# 505153_2_1.net
KiCad netlist of a schematic drawn in Altium Designer
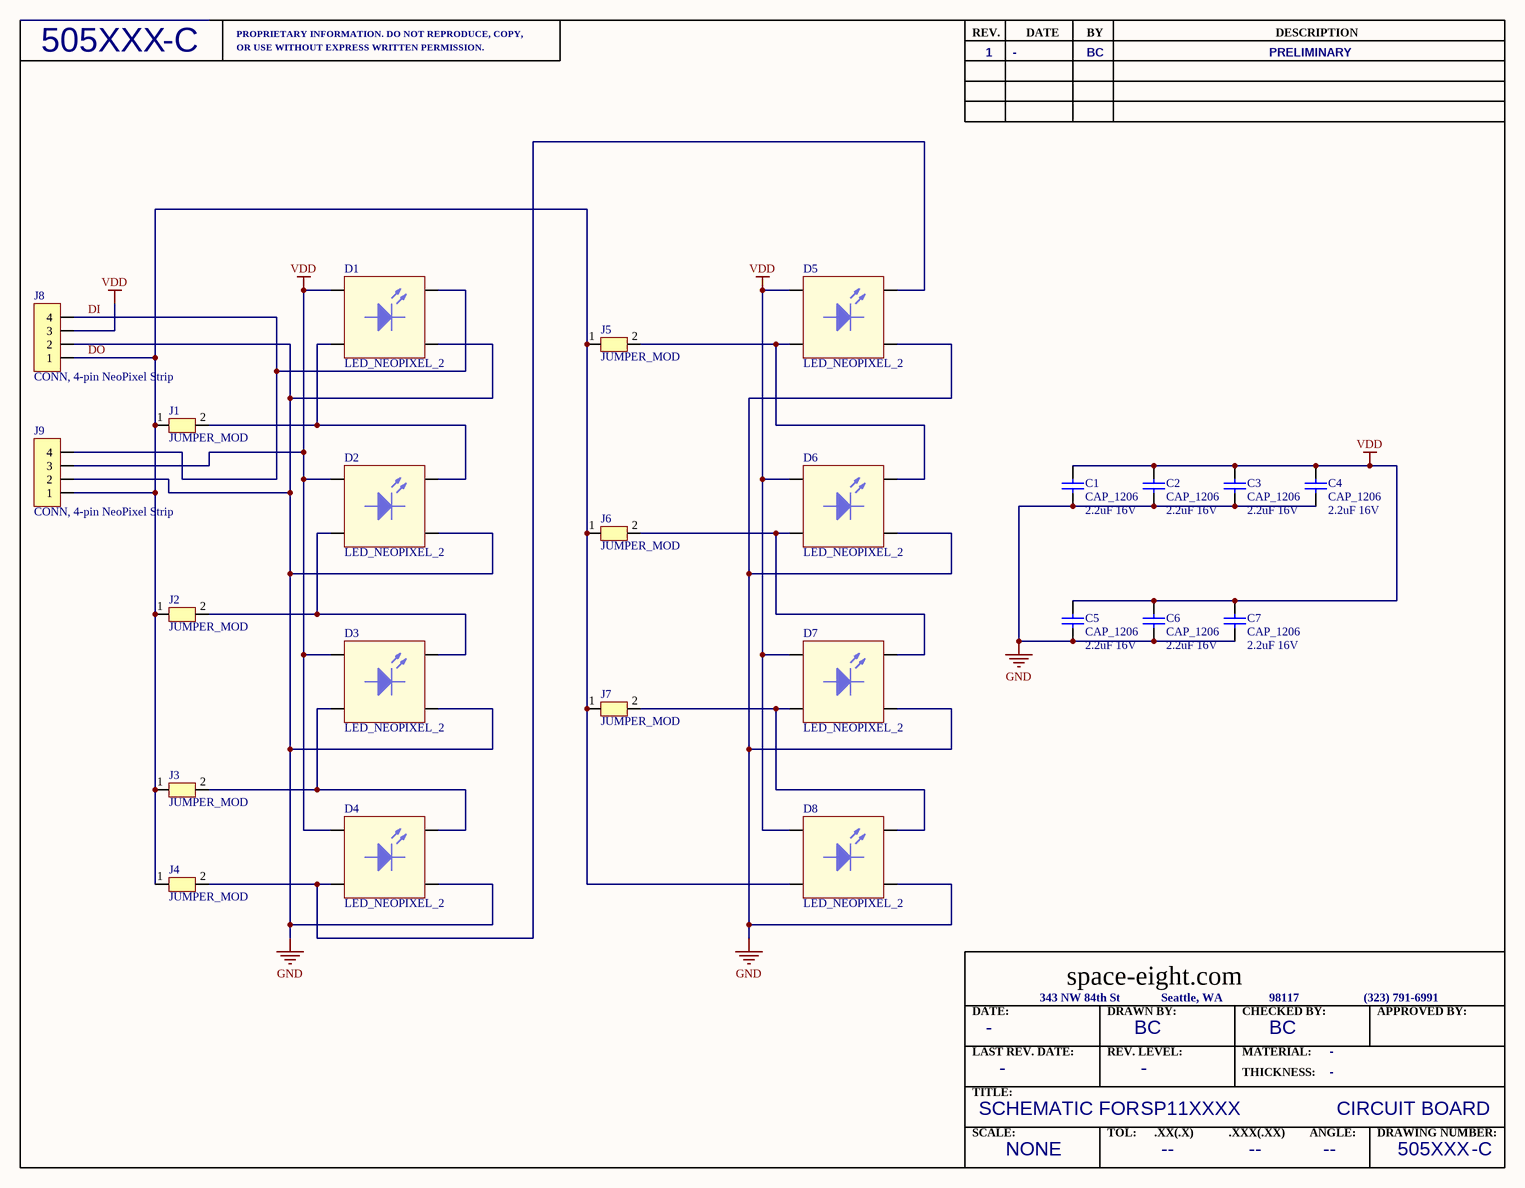
[diagram p0: 505153_2_1.SchDoc]

(export (version "E")
  (design (tool "Eeschema 10.0.6"))
  (components
    (comp (ref "C1")
      (value "CAP_1206")
      (footprint "SMT_1206_MOD")
      (description "CAP")
      (fields
        (field (name "MANUFACTURER") "Generic Components")
        (field (name "ALTIUM_VALUE") "2.2uF 16V")
        (field (name "PUBLISHER") "Altium Limited")
      )
      (libsource (lib "Custom_Lib_2") (part "CAP_1206"))
    )
    (comp (ref "C2")
      (value "CAP_1206")
      (footprint "SMT_1206_MOD")
      (description "CAP")
      (fields
        (field (name "MANUFACTURER") "Generic Components")
        (field (name "ALTIUM_VALUE") "2.2uF 16V")
        (field (name "PUBLISHER") "Altium Limited")
      )
      (libsource (lib "Custom_Lib_2") (part "CAP_1206"))
    )
    (comp (ref "C3")
      (value "CAP_1206")
      (footprint "SMT_1206_MOD")
      (description "CAP")
      (fields
        (field (name "MANUFACTURER") "Generic Components")
        (field (name "ALTIUM_VALUE") "2.2uF 16V")
        (field (name "PUBLISHER") "Altium Limited")
      )
      (libsource (lib "Custom_Lib_2") (part "CAP_1206"))
    )
    (comp (ref "C4")
      (value "CAP_1206")
      (footprint "SMT_1206_MOD")
      (description "CAP")
      (fields
        (field (name "MANUFACTURER") "Generic Components")
        (field (name "ALTIUM_VALUE") "2.2uF 16V")
        (field (name "PUBLISHER") "Altium Limited")
      )
      (libsource (lib "Custom_Lib_2") (part "CAP_1206"))
    )
    (comp (ref "C5")
      (value "CAP_1206")
      (footprint "SMT_1206_MOD")
      (description "CAP")
      (fields
        (field (name "MANUFACTURER") "Generic Components")
        (field (name "ALTIUM_VALUE") "2.2uF 16V")
        (field (name "PUBLISHER") "Altium Limited")
      )
      (libsource (lib "Custom_Lib_2") (part "CAP_1206"))
    )
    (comp (ref "C6")
      (value "CAP_1206")
      (footprint "SMT_1206_MOD")
      (description "CAP")
      (fields
        (field (name "MANUFACTURER") "Generic Components")
        (field (name "ALTIUM_VALUE") "2.2uF 16V")
        (field (name "PUBLISHER") "Altium Limited")
      )
      (libsource (lib "Custom_Lib_2") (part "CAP_1206"))
    )
    (comp (ref "C7")
      (value "CAP_1206")
      (footprint "SMT_1206_MOD")
      (description "CAP")
      (fields
        (field (name "MANUFACTURER") "Generic Components")
        (field (name "ALTIUM_VALUE") "2.2uF 16V")
        (field (name "PUBLISHER") "Altium Limited")
      )
      (libsource (lib "Custom_Lib_2") (part "CAP_1206"))
    )
    (comp (ref "D1")
      (value "LED_NEOPIXEL_2")
      (footprint "NEOPIXEL_2")
      (description "RGB NEOPIXEL")
      (fields (field (name "MANUFACTURER") "Generic Components") (field (name "PUBLISHER") "Altium Limited"))
      (libsource (lib "Custom_Lib_2") (part "LED_NEOPIXEL_2"))
    )
    (comp (ref "D2")
      (value "LED_NEOPIXEL_2")
      (footprint "NEOPIXEL_2")
      (description "RGB NEOPIXEL")
      (fields (field (name "MANUFACTURER") "Generic Components") (field (name "PUBLISHER") "Altium Limited"))
      (libsource (lib "Custom_Lib_2") (part "LED_NEOPIXEL_2"))
    )
    (comp (ref "D3")
      (value "LED_NEOPIXEL_2")
      (footprint "NEOPIXEL_2")
      (description "RGB NEOPIXEL")
      (fields (field (name "MANUFACTURER") "Generic Components") (field (name "PUBLISHER") "Altium Limited"))
      (libsource (lib "Custom_Lib_2") (part "LED_NEOPIXEL_2"))
    )
    (comp (ref "D4")
      (value "LED_NEOPIXEL_2")
      (footprint "NEOPIXEL_2")
      (description "RGB NEOPIXEL")
      (fields (field (name "MANUFACTURER") "Generic Components") (field (name "PUBLISHER") "Altium Limited"))
      (libsource (lib "Custom_Lib_2") (part "LED_NEOPIXEL_2"))
    )
    (comp (ref "D5")
      (value "LED_NEOPIXEL_2")
      (footprint "NEOPIXEL_2")
      (description "RGB NEOPIXEL")
      (fields (field (name "MANUFACTURER") "Generic Components") (field (name "PUBLISHER") "Altium Limited"))
      (libsource (lib "Custom_Lib_2") (part "LED_NEOPIXEL_2"))
    )
    (comp (ref "D6")
      (value "LED_NEOPIXEL_2")
      (footprint "NEOPIXEL_2")
      (description "RGB NEOPIXEL")
      (fields (field (name "MANUFACTURER") "Generic Components") (field (name "PUBLISHER") "Altium Limited"))
      (libsource (lib "Custom_Lib_2") (part "LED_NEOPIXEL_2"))
    )
    (comp (ref "D7")
      (value "LED_NEOPIXEL_2")
      (footprint "NEOPIXEL_2")
      (description "RGB NEOPIXEL")
      (fields (field (name "MANUFACTURER") "Generic Components") (field (name "PUBLISHER") "Altium Limited"))
      (libsource (lib "Custom_Lib_2") (part "LED_NEOPIXEL_2"))
    )
    (comp (ref "D8")
      (value "LED_NEOPIXEL_2")
      (footprint "NEOPIXEL_2")
      (description "RGB NEOPIXEL")
      (fields (field (name "MANUFACTURER") "Generic Components") (field (name "PUBLISHER") "Altium Limited"))
      (libsource (lib "Custom_Lib_2") (part "LED_NEOPIXEL_2"))
    )
    (comp (ref "J1")
      (value "JUMPER_MOD")
      (footprint "JUMPER_SMT")
      (libsource (lib "Custom_Lib_2") (part "JUMPER_MOD"))
    )
    (comp (ref "J2")
      (value "JUMPER_MOD")
      (footprint "JUMPER_SMT")
      (libsource (lib "Custom_Lib_2") (part "JUMPER_MOD"))
    )
    (comp (ref "J3")
      (value "JUMPER_MOD")
      (footprint "JUMPER_SMT")
      (libsource (lib "Custom_Lib_2") (part "JUMPER_MOD"))
    )
    (comp (ref "J4")
      (value "JUMPER_MOD")
      (footprint "JUMPER_SMT")
      (libsource (lib "Custom_Lib_2") (part "JUMPER_MOD"))
    )
    (comp (ref "J5")
      (value "JUMPER_MOD")
      (footprint "JUMPER_SMT")
      (libsource (lib "Custom_Lib_2") (part "JUMPER_MOD"))
    )
    (comp (ref "J6")
      (value "JUMPER_MOD")
      (footprint "JUMPER_SMT")
      (libsource (lib "Custom_Lib_2") (part "JUMPER_MOD"))
    )
    (comp (ref "J7")
      (value "JUMPER_MOD")
      (footprint "JUMPER_SMT")
      (libsource (lib "Custom_Lib_2") (part "JUMPER_MOD"))
    )
    (comp (ref "J8")
      (value "CONN, 4-pin NeoPixel Strip")
      (footprint "CONN_NEOPIXEL_1")
      (description "Conn Neopixel Strip")
      (fields (field (name "PUBLISHER") "Altium Limited"))
      (libsource (lib "Custom_Lib_2") (part "CONN, 4-pin NeoPixel Strip"))
    )
    (comp (ref "J9")
      (value "CONN, 4-pin NeoPixel Strip")
      (footprint "CONN_NEOPIXEL_1")
      (description "Conn Neopixel Strip")
      (fields (field (name "PUBLISHER") "Altium Limited"))
      (libsource (lib "Custom_Lib_2") (part "CONN, 4-pin NeoPixel Strip"))
    )
  )
  (nets
    (net (code "1") (name "/DI") (class "Default")
      (node (ref "D1") (pin "2") (pinfunction "DI_2") (pintype "passive"))
      (node (ref "J8") (pin "4") (pinfunction "4_4") (pintype "passive"))
      (node (ref "J9") (pin "4") (pinfunction "4_4") (pintype "passive"))
    )
    (net (code "2") (name "/DO") (class "Default")
      (node (ref "D8") (pin "4") (pinfunction "DO_4") (pintype "passive"))
      (node (ref "J1") (pin "1") (pinfunction "I/_1") (pintype "passive"))
      (node (ref "J2") (pin "1") (pinfunction "I/_1") (pintype "passive"))
      (node (ref "J3") (pin "1") (pinfunction "I/_1") (pintype "passive"))
      (node (ref "J4") (pin "1") (pinfunction "I/_1") (pintype "passive"))
      (node (ref "J5") (pin "1") (pinfunction "I/_1") (pintype "passive"))
      (node (ref "J6") (pin "1") (pinfunction "I/_1") (pintype "passive"))
      (node (ref "J7") (pin "1") (pinfunction "I/_1") (pintype "passive"))
      (node (ref "J8") (pin "1") (pinfunction "1_1") (pintype "passive"))
      (node (ref "J9") (pin "1") (pinfunction "1_1") (pintype "passive"))
    )
    (net (code "3") (name "GND") (class "Default")
      (node (ref "C1") (pin "1") (pinfunction "1_1") (pintype "passive"))
      (node (ref "C2") (pin "1") (pinfunction "1_1") (pintype "passive"))
      (node (ref "C3") (pin "1") (pinfunction "1_1") (pintype "passive"))
      (node (ref "C4") (pin "1") (pinfunction "1_1") (pintype "passive"))
      (node (ref "C5") (pin "1") (pinfunction "1_1") (pintype "passive"))
      (node (ref "C6") (pin "1") (pinfunction "1_1") (pintype "passive"))
      (node (ref "C7") (pin "1") (pinfunction "1_1") (pintype "passive"))
      (node (ref "D1") (pin "1") (pinfunction "GND_1") (pintype "passive"))
      (node (ref "D2") (pin "1") (pinfunction "GND_1") (pintype "passive"))
      (node (ref "D3") (pin "1") (pinfunction "GND_1") (pintype "passive"))
      (node (ref "D4") (pin "1") (pinfunction "GND_1") (pintype "passive"))
      (node (ref "D5") (pin "1") (pinfunction "GND_1") (pintype "passive"))
      (node (ref "D6") (pin "1") (pinfunction "GND_1") (pintype "passive"))
      (node (ref "D7") (pin "1") (pinfunction "GND_1") (pintype "passive"))
      (node (ref "D8") (pin "1") (pinfunction "GND_1") (pintype "passive"))
      (node (ref "J8") (pin "2") (pinfunction "2_2") (pintype "passive"))
      (node (ref "J9") (pin "2") (pinfunction "2_2") (pintype "passive"))
    )
    (net (code "4") (name "Net-(D1-DO)") (class "Default")
      (node (ref "D1") (pin "4") (pinfunction "DO_4") (pintype "passive"))
      (node (ref "D2") (pin "2") (pinfunction "DI_2") (pintype "passive"))
      (node (ref "J1") (pin "2") (pinfunction "O_2") (pintype "passive"))
    )
    (net (code "5") (name "Net-(D2-DO)") (class "Default")
      (node (ref "D2") (pin "4") (pinfunction "DO_4") (pintype "passive"))
      (node (ref "D3") (pin "2") (pinfunction "DI_2") (pintype "passive"))
      (node (ref "J2") (pin "2") (pinfunction "O_2") (pintype "passive"))
    )
    (net (code "6") (name "Net-(D3-DO)") (class "Default")
      (node (ref "D3") (pin "4") (pinfunction "DO_4") (pintype "passive"))
      (node (ref "D4") (pin "2") (pinfunction "DI_2") (pintype "passive"))
      (node (ref "J3") (pin "2") (pinfunction "O_2") (pintype "passive"))
    )
    (net (code "7") (name "Net-(D4-DO)") (class "Default")
      (node (ref "D4") (pin "4") (pinfunction "DO_4") (pintype "passive"))
      (node (ref "D5") (pin "2") (pinfunction "DI_2") (pintype "passive"))
      (node (ref "J4") (pin "2") (pinfunction "O_2") (pintype "passive"))
    )
    (net (code "8") (name "Net-(D5-DO)") (class "Default")
      (node (ref "D5") (pin "4") (pinfunction "DO_4") (pintype "passive"))
      (node (ref "D6") (pin "2") (pinfunction "DI_2") (pintype "passive"))
      (node (ref "J5") (pin "2") (pinfunction "O_2") (pintype "passive"))
    )
    (net (code "9") (name "Net-(D6-DO)") (class "Default")
      (node (ref "D6") (pin "4") (pinfunction "DO_4") (pintype "passive"))
      (node (ref "D7") (pin "2") (pinfunction "DI_2") (pintype "passive"))
      (node (ref "J6") (pin "2") (pinfunction "O_2") (pintype "passive"))
    )
    (net (code "10") (name "Net-(D7-DO)") (class "Default")
      (node (ref "D7") (pin "4") (pinfunction "DO_4") (pintype "passive"))
      (node (ref "D8") (pin "2") (pinfunction "DI_2") (pintype "passive"))
      (node (ref "J7") (pin "2") (pinfunction "O_2") (pintype "passive"))
    )
    (net (code "11") (name "VDD") (class "Default")
      (node (ref "C1") (pin "2") (pinfunction "2_2") (pintype "passive"))
      (node (ref "C2") (pin "2") (pinfunction "2_2") (pintype "passive"))
      (node (ref "C3") (pin "2") (pinfunction "2_2") (pintype "passive"))
      (node (ref "C4") (pin "2") (pinfunction "2_2") (pintype "passive"))
      (node (ref "C5") (pin "2") (pinfunction "2_2") (pintype "passive"))
      (node (ref "C6") (pin "2") (pinfunction "2_2") (pintype "passive"))
      (node (ref "C7") (pin "2") (pinfunction "2_2") (pintype "passive"))
      (node (ref "D1") (pin "3") (pinfunction "VDD_3") (pintype "passive"))
      (node (ref "D2") (pin "3") (pinfunction "VDD_3") (pintype "passive"))
      (node (ref "D3") (pin "3") (pinfunction "VDD_3") (pintype "passive"))
      (node (ref "D4") (pin "3") (pinfunction "VDD_3") (pintype "passive"))
      (node (ref "D5") (pin "3") (pinfunction "VDD_3") (pintype "passive"))
      (node (ref "D6") (pin "3") (pinfunction "VDD_3") (pintype "passive"))
      (node (ref "D7") (pin "3") (pinfunction "VDD_3") (pintype "passive"))
      (node (ref "D8") (pin "3") (pinfunction "VDD_3") (pintype "passive"))
      (node (ref "J8") (pin "3") (pinfunction "3_3") (pintype "passive"))
      (node (ref "J9") (pin "3") (pinfunction "3_3") (pintype "passive"))
    )
  )
)
